# sparrow_ble.net
KiCad netlist of a schematic drawn in EAGLE
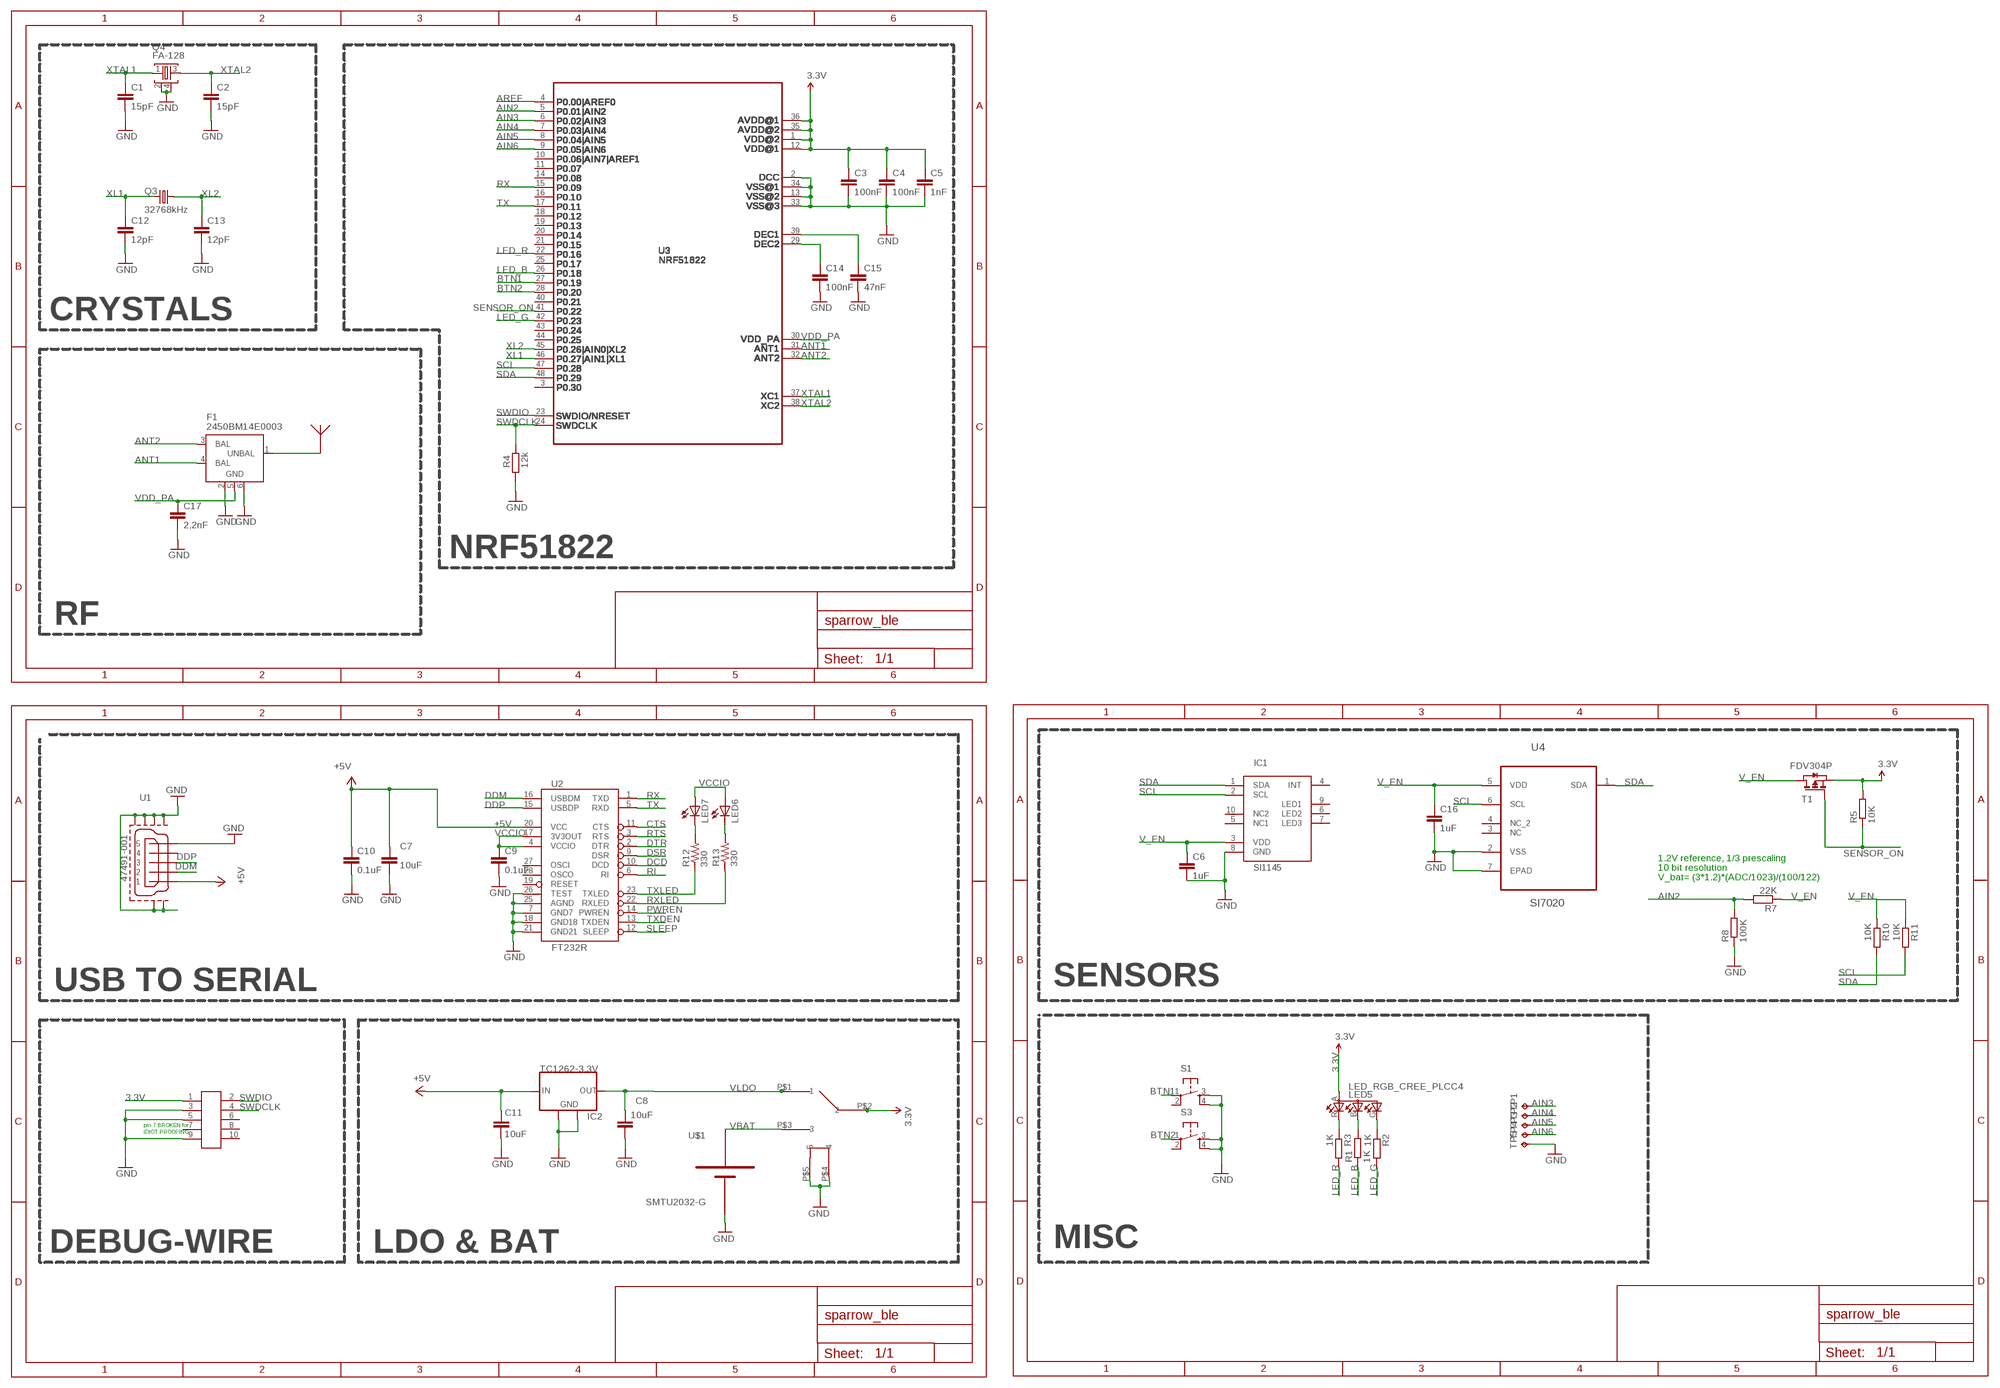
[diagram p0: schematic, sheet 1]

(export (version "E")
  (design (tool "Eeschema 10.0.6"))
  (components
    (comp (ref "C1")
      (value "15pF")
      (footprint "eagle-import:C0402")
      (libsource (lib "eagle-import") (part "resistor_C-EUC0402"))
    )
    (comp (ref "C2")
      (value "15pF")
      (footprint "eagle-import:C0402")
      (libsource (lib "eagle-import") (part "resistor_C-EUC0402"))
    )
    (comp (ref "C3")
      (value "100nF")
      (footprint "eagle-import:C0402")
      (libsource (lib "eagle-import") (part "resistor_C-EUC0402"))
    )
    (comp (ref "C4")
      (value "100nF")
      (footprint "eagle-import:C0402")
      (libsource (lib "eagle-import") (part "resistor_C-EUC0402"))
    )
    (comp (ref "C5")
      (value "1nF")
      (footprint "eagle-import:C0402")
      (libsource (lib "eagle-import") (part "resistor_C-EUC0402"))
    )
    (comp (ref "C6")
      (value "1uF")
      (footprint "eagle-import:C0402")
      (libsource (lib "eagle-import") (part "resistor_C-EUC0402"))
    )
    (comp (ref "C7")
      (value "10uF")
      (footprint "eagle-import:C0402")
      (libsource (lib "eagle-import") (part "C-EUC0402"))
    )
    (comp (ref "C8")
      (value "10uF")
      (footprint "eagle-import:C0402")
      (libsource (lib "eagle-import") (part "C-EUC0402"))
    )
    (comp (ref "C9")
      (value "0.1uF")
      (footprint "eagle-import:0402-CAP")
      (libsource (lib "eagle-import") (part "CAP0402-CAP"))
    )
    (comp (ref "C10")
      (value "0.1uF")
      (footprint "eagle-import:0402-CAP")
      (libsource (lib "eagle-import") (part "CAP0402-CAP"))
    )
    (comp (ref "C11")
      (value "10uF")
      (footprint "eagle-import:C0402")
      (libsource (lib "eagle-import") (part "C-EUC0402"))
    )
    (comp (ref "C12")
      (value "12pF")
      (footprint "eagle-import:C0402")
      (libsource (lib "eagle-import") (part "resistor_C-EUC0402"))
    )
    (comp (ref "C13")
      (value "12pF")
      (footprint "eagle-import:C0402")
      (libsource (lib "eagle-import") (part "resistor_C-EUC0402"))
    )
    (comp (ref "C14")
      (value "100nF")
      (footprint "eagle-import:C0402")
      (libsource (lib "eagle-import") (part "resistor_C-EUC0402"))
    )
    (comp (ref "C15")
      (value "47nF")
      (footprint "eagle-import:C0402")
      (libsource (lib "eagle-import") (part "resistor_C-EUC0402"))
    )
    (comp (ref "C16")
      (value "1uF")
      (footprint "eagle-import:C0402")
      (libsource (lib "eagle-import") (part "resistor_C-EUC0402"))
    )
    (comp (ref "C17")
      (value "2,2nF")
      (footprint "eagle-import:C0402")
      (libsource (lib "eagle-import") (part "resistor_C-EUC0402"))
    )
    (comp (ref "F1")
      (value "2450BM14E0003")
      (footprint "eagle-import:2450BM15A0002")
      (libsource (lib "eagle-import") (part "2450BM15A0002"))
    )
    (comp (ref "IC1")
      (value "SI1145")
      (footprint "eagle-import:QFN10")
      (libsource (lib "eagle-import") (part "SI1145"))
    )
    (comp (ref "IC2")
      (value "TC1262-3.3V")
      (footprint "eagle-import:SOT223")
      (libsource (lib "eagle-import") (part "MCP1825S-SOT223"))
    )
    (comp (ref "J3")
      (value "SMALL_HEADER_5X2")
      (footprint "eagle-import:SAMTEC_5X2")
      (libsource (lib "eagle-import") (part "SMALL_HEADER_5X2"))
    )
    (comp (ref "LED5")
      (value "LED_RGB_CREE_PLCC4")
      (footprint "eagle-import:P-LCC-4-4")
      (libsource (lib "eagle-import") (part "LED_RGB_CREE_PLCC4"))
    )
    (comp (ref "LED6")
      (value "LEDCHIP-LED0603")
      (footprint "eagle-import:CHIP-LED0603")
      (libsource (lib "eagle-import") (part "LEDCHIP-LED0603"))
    )
    (comp (ref "LED7")
      (value "LEDCHIP-LED0603")
      (footprint "eagle-import:CHIP-LED0603")
      (libsource (lib "eagle-import") (part "LEDCHIP-LED0603"))
    )
    (comp (ref "Q3")
      (value "32768kHz")
      (footprint "eagle-import:FC-12M")
      (libsource (lib "eagle-import") (part "FC-12M"))
    )
    (comp (ref "Q4")
      (value "FA-128")
      (footprint "eagle-import:FA-128")
      (libsource (lib "eagle-import") (part "FA-128"))
    )
    (comp (ref "R1")
      (value "1K")
      (footprint "eagle-import:R0402")
      (libsource (lib "eagle-import") (part "R-EU_R0402"))
    )
    (comp (ref "R2")
      (value "1K")
      (footprint "eagle-import:R0402")
      (libsource (lib "eagle-import") (part "R-EU_R0402"))
    )
    (comp (ref "R3")
      (value "1K")
      (footprint "eagle-import:R0402")
      (libsource (lib "eagle-import") (part "R-EU_R0402"))
    )
    (comp (ref "R4")
      (value "12k")
      (footprint "eagle-import:R0402")
      (libsource (lib "eagle-import") (part "resistor_R-EU_R0402"))
    )
    (comp (ref "R5")
      (value "10K")
      (footprint "eagle-import:R0402")
      (libsource (lib "eagle-import") (part "resistor_R-EU_R0402"))
    )
    (comp (ref "R7")
      (value "22K")
      (footprint "eagle-import:R0402")
      (libsource (lib "eagle-import") (part "resistor_R-EU_R0402"))
    )
    (comp (ref "R8")
      (value "100K")
      (footprint "eagle-import:R0402")
      (libsource (lib "eagle-import") (part "resistor_R-EU_R0402"))
    )
    (comp (ref "R10")
      (value "10K")
      (footprint "eagle-import:R0402")
      (libsource (lib "eagle-import") (part "resistor_R-EU_R0402"))
    )
    (comp (ref "R11")
      (value "10K")
      (footprint "eagle-import:R0402")
      (libsource (lib "eagle-import") (part "resistor_R-EU_R0402"))
    )
    (comp (ref "R12")
      (value "330")
      (footprint "eagle-import:0402-RES")
      (libsource (lib "eagle-import") (part "RESISTOR0402-RES"))
    )
    (comp (ref "R13")
      (value "330")
      (footprint "eagle-import:0402-RES")
      (libsource (lib "eagle-import") (part "RESISTOR0402-RES"))
    )
    (comp (ref "S1")
      (value "TAC_SWITCHSMD")
      (footprint "eagle-import:TACTILE-SWITCH-SMD")
      (libsource (lib "eagle-import") (part "TAC_SWITCHSMD"))
    )
    (comp (ref "S3")
      (value "TAC_SWITCHSMD")
      (footprint "eagle-import:TACTILE-SWITCH-SMD")
      (libsource (lib "eagle-import") (part "TAC_SWITCHSMD"))
    )
    (comp (ref "T1")
      (value "FDV304P")
      (footprint "eagle-import:SOT-23")
      (libsource (lib "eagle-import") (part "PMOSSOT23"))
    )
    (comp (ref "TP1")
      (value "TPTP16R")
      (footprint "eagle-import:TP16R")
      (libsource (lib "eagle-import") (part "TPTP16R"))
    )
    (comp (ref "TP2")
      (value "TPTP16R")
      (footprint "eagle-import:TP16R")
      (libsource (lib "eagle-import") (part "TPTP16R"))
    )
    (comp (ref "TP3")
      (value "TPTP16R")
      (footprint "eagle-import:TP16R")
      (libsource (lib "eagle-import") (part "TPTP16R"))
    )
    (comp (ref "TP4")
      (value "TPTP16R")
      (footprint "eagle-import:TP16R")
      (libsource (lib "eagle-import") (part "TPTP16R"))
    )
    (comp (ref "TP5")
      (value "TPTP16R")
      (footprint "eagle-import:TP16R")
      (libsource (lib "eagle-import") (part "TPTP16R"))
    )
    (comp (ref "U$1")
      (value "SMTU2032-G")
      (footprint "eagle-import:SMTU2032-G")
      (libsource (lib "eagle-import") (part "SMTU2032-G"))
    )
    (comp (ref "U$2")
      (value "SWITCH")
      (footprint "eagle-import:PCM12")
      (libsource (lib "eagle-import") (part "SWITCH"))
    )
    (comp (ref "U1")
      (value "47491-001")
      (footprint "eagle-import:47491-0001")
      (libsource (lib "eagle-import") (part "47491-001"))
    )
    (comp (ref "U2")
      (value "FT232R")
      (footprint "eagle-import:SSOP28DB")
      (libsource (lib "eagle-import") (part "FT232RLSSOP"))
    )
    (comp (ref "U3")
      (value "NRF51822")
      (footprint "eagle-import:NRF51822-QFN48")
      (libsource (lib "eagle-import") (part "NRF51822"))
    )
    (comp (ref "U4")
      (value "SI7020")
      (footprint "eagle-import:DFN300X300X110-7N")
      (fields (field (name "MPN") "SHT21"))
      (libsource (lib "eagle-import") (part "SHT21"))
    )
    (comp (ref "U8")
      (value "ANTENNA")
      (footprint "eagle-import:ANTPACK")
      (libsource (lib "eagle-import") (part "ANTENNA"))
    )
  )
  (nets
    (net (code "1") (name "+5V") (class "Default")
      (node (ref "C10") (pin "1") (pinfunction "1_1") (pintype "passive"))
      (node (ref "C11") (pin "1") (pinfunction "1_1") (pintype "passive"))
      (node (ref "C7") (pin "1") (pinfunction "1_1") (pintype "passive"))
      (node (ref "IC2") (pin "1") (pinfunction "IN_1") (pintype "input"))
      (node (ref "U1") (pin "1") (pinfunction "1_1") (pintype "input"))
      (node (ref "U2") (pin "20") (pinfunction "VCC_20") (pintype "power_in"))
    )
    (net (code "2") (name "/AIN2") (class "Default")
      (node (ref "R7") (pin "2") (pinfunction "2_2") (pintype "passive"))
      (node (ref "R8") (pin "2") (pinfunction "2_2") (pintype "passive"))
      (node (ref "U3") (pin "5") (pinfunction "1_5") (pintype "bidirectional"))
    )
    (net (code "3") (name "/AIN3") (class "Default")
      (node (ref "TP1") (pin "TP") (pinfunction "TP_TP") (pintype "input"))
      (node (ref "U3") (pin "6") (pinfunction "1_6") (pintype "bidirectional"))
    )
    (net (code "4") (name "/AIN4") (class "Default")
      (node (ref "TP2") (pin "TP") (pinfunction "TP_TP") (pintype "input"))
      (node (ref "U3") (pin "7") (pinfunction "1_7") (pintype "bidirectional"))
    )
    (net (code "5") (name "/AIN5") (class "Default")
      (node (ref "TP3") (pin "TP") (pinfunction "TP_TP") (pintype "input"))
      (node (ref "U3") (pin "8") (pinfunction "1_8") (pintype "bidirectional"))
    )
    (net (code "6") (name "/AIN6") (class "Default")
      (node (ref "TP4") (pin "TP") (pinfunction "TP_TP") (pintype "input"))
      (node (ref "U3") (pin "9") (pinfunction "1_9") (pintype "bidirectional"))
    )
    (net (code "7") (name "/ANT1") (class "Default")
      (node (ref "F1") (pin "4") (pinfunction "BAL_4") (pintype "passive"))
      (node (ref "U3") (pin "31") (pinfunction "1_31") (pintype "bidirectional"))
    )
    (net (code "8") (name "/ANT2") (class "Default")
      (node (ref "F1") (pin "3") (pinfunction "BAL_3") (pintype "passive"))
      (node (ref "U3") (pin "32") (pinfunction "1_32") (pintype "bidirectional"))
    )
    (net (code "9") (name "/AREF") (class "Default")
      (node (ref "U3") (pin "4") (pinfunction "1_4") (pintype "bidirectional"))
    )
    (net (code "10") (name "/BTN1") (class "Default")
      (node (ref "S1") (pin "1") (pinfunction "1_1") (pintype "passive"))
      (node (ref "U3") (pin "27") (pinfunction "1_27") (pintype "bidirectional"))
    )
    (net (code "11") (name "/BTN2") (class "Default")
      (node (ref "S3") (pin "1") (pinfunction "1_1") (pintype "passive"))
      (node (ref "U3") (pin "28") (pinfunction "1_28") (pintype "bidirectional"))
    )
    (net (code "12") (name "/CTS") (class "Default")
      (node (ref "U2") (pin "11") (pinfunction "CTS_11") (pintype "input"))
    )
    (net (code "13") (name "/DCD") (class "Default")
      (node (ref "U2") (pin "10") (pinfunction "DCD_10") (pintype "input"))
    )
    (net (code "14") (name "/DDM") (class "Default")
      (node (ref "U1") (pin "2") (pinfunction "2_2") (pintype "input"))
      (node (ref "U2") (pin "16") (pinfunction "USBDM_16") (pintype "bidirectional"))
    )
    (net (code "15") (name "/DDP") (class "Default")
      (node (ref "U1") (pin "3") (pinfunction "3_3") (pintype "input"))
      (node (ref "U2") (pin "15") (pinfunction "USBDP_15") (pintype "bidirectional"))
    )
    (net (code "16") (name "/DSR") (class "Default")
      (node (ref "U2") (pin "9") (pinfunction "DSR_9") (pintype "input"))
    )
    (net (code "17") (name "/DTR") (class "Default")
      (node (ref "U2") (pin "2") (pinfunction "DTR_2") (pintype "output"))
    )
    (net (code "18") (name "/LED_B") (class "Default")
      (node (ref "R1") (pin "1") (pinfunction "1_1") (pintype "passive"))
      (node (ref "U3") (pin "26") (pinfunction "1_26") (pintype "bidirectional"))
    )
    (net (code "19") (name "/LED_G") (class "Default")
      (node (ref "R2") (pin "2") (pinfunction "2_2") (pintype "passive"))
      (node (ref "U3") (pin "42") (pinfunction "1_42") (pintype "bidirectional"))
    )
    (net (code "20") (name "/LED_R") (class "Default")
      (node (ref "R3") (pin "2") (pinfunction "2_2") (pintype "passive"))
      (node (ref "U3") (pin "22") (pinfunction "1_22") (pintype "bidirectional"))
    )
    (net (code "21") (name "/PWREN") (class "Default")
      (node (ref "U2") (pin "14") (pinfunction "PWREN_14") (pintype "input"))
    )
    (net (code "22") (name "/RI") (class "Default")
      (node (ref "U2") (pin "6") (pinfunction "RI_6") (pintype "input"))
    )
    (net (code "23") (name "/RTS") (class "Default")
      (node (ref "U2") (pin "3") (pinfunction "RTS_3") (pintype "output"))
    )
    (net (code "24") (name "/RX") (class "Default")
      (node (ref "U2") (pin "1") (pinfunction "TXD_1") (pintype "output"))
      (node (ref "U3") (pin "15") (pinfunction "1_15") (pintype "bidirectional"))
    )
    (net (code "25") (name "/RXLED") (class "Default")
      (node (ref "R13") (pin "1") (pinfunction "1_1") (pintype "passive"))
      (node (ref "U2") (pin "22") (pinfunction "RXLED_22") (pintype "input"))
    )
    (net (code "26") (name "/SCL") (class "Default")
      (node (ref "IC1") (pin "2") (pinfunction "SCL_2") (pintype "bidirectional"))
      (node (ref "R11") (pin "2") (pinfunction "2_2") (pintype "passive"))
      (node (ref "U3") (pin "47") (pinfunction "1_47") (pintype "bidirectional"))
      (node (ref "U4") (pin "6") (pinfunction "SCL_6") (pintype "input"))
    )
    (net (code "27") (name "/SDA") (class "Default")
      (node (ref "IC1") (pin "1") (pinfunction "SDA_1") (pintype "bidirectional"))
      (node (ref "R10") (pin "2") (pinfunction "2_2") (pintype "passive"))
      (node (ref "U3") (pin "48") (pinfunction "1_48") (pintype "bidirectional"))
      (node (ref "U4") (pin "1") (pinfunction "SDA_1") (pintype "bidirectional"))
    )
    (net (code "28") (name "/SENSOR_ON") (class "Default")
      (node (ref "R5") (pin "1") (pinfunction "1_1") (pintype "passive"))
      (node (ref "T1") (pin "3") (pinfunction "G_3") (pintype "passive"))
      (node (ref "U3") (pin "41") (pinfunction "1_41") (pintype "bidirectional"))
    )
    (net (code "29") (name "/SLEEP") (class "Default")
      (node (ref "U2") (pin "12") (pinfunction "SLEEP_12") (pintype "input"))
    )
    (net (code "30") (name "/SWDCLK") (class "Default")
      (node (ref "J3") (pin "4") (pinfunction "P$4_4") (pintype "bidirectional"))
      (node (ref "R4") (pin "2") (pinfunction "2_2") (pintype "passive"))
      (node (ref "U3") (pin "24") (pinfunction "1_24") (pintype "bidirectional"))
    )
    (net (code "31") (name "/SWDIO") (class "Default")
      (node (ref "J3") (pin "2") (pinfunction "P$2_2") (pintype "bidirectional"))
      (node (ref "U3") (pin "23") (pinfunction "1_23") (pintype "bidirectional"))
    )
    (net (code "32") (name "/TX") (class "Default")
      (node (ref "U2") (pin "5") (pinfunction "RXD_5") (pintype "input"))
      (node (ref "U3") (pin "17") (pinfunction "1_17") (pintype "bidirectional"))
    )
    (net (code "33") (name "/TXDEN") (class "Default")
      (node (ref "U2") (pin "13") (pinfunction "TXDEN_13") (pintype "input"))
    )
    (net (code "34") (name "/TXLED") (class "Default")
      (node (ref "R12") (pin "1") (pinfunction "1_1") (pintype "passive"))
      (node (ref "U2") (pin "23") (pinfunction "TXLED_23") (pintype "input"))
    )
    (net (code "35") (name "/VBAT") (class "Default")
      (node (ref "U$1") (pin "1") (pinfunction "P$1_1") (pintype "bidirectional"))
      (node (ref "U$2") (pin "P$3") (pinfunction "3_P$3") (pintype "bidirectional"))
    )
    (net (code "36") (name "/VCCIO") (class "Default")
      (node (ref "C9") (pin "1") (pinfunction "1_1") (pintype "passive"))
      (node (ref "LED6") (pin "A") (pinfunction "A_A") (pintype "passive"))
      (node (ref "LED7") (pin "A") (pinfunction "A_A") (pintype "passive"))
      (node (ref "U2") (pin "17") (pinfunction "3V3OUT_17") (pintype "output"))
      (node (ref "U2") (pin "4") (pinfunction "VCCIO_4") (pintype "power_in"))
    )
    (net (code "37") (name "/VDD_PA") (class "Default")
      (node (ref "C17") (pin "1") (pinfunction "1_1") (pintype "passive"))
      (node (ref "F1") (pin "5") (pinfunction "GND_5") (pintype "passive"))
      (node (ref "U3") (pin "30") (pinfunction "1_30") (pintype "output"))
    )
    (net (code "38") (name "/VLDO") (class "Default")
      (node (ref "C8") (pin "1") (pinfunction "1_1") (pintype "passive"))
      (node (ref "IC2") (pin "3") (pinfunction "OUT_3") (pintype "output"))
      (node (ref "U$2") (pin "P$1") (pinfunction "1_P$1") (pintype "bidirectional"))
    )
    (net (code "39") (name "/V_EN") (class "Default")
      (node (ref "C16") (pin "1") (pinfunction "1_1") (pintype "passive"))
      (node (ref "C6") (pin "1") (pinfunction "1_1") (pintype "passive"))
      (node (ref "IC1") (pin "3") (pinfunction "VDD_3") (pintype "bidirectional"))
      (node (ref "R10") (pin "1") (pinfunction "1_1") (pintype "passive"))
      (node (ref "R11") (pin "1") (pinfunction "1_1") (pintype "passive"))
      (node (ref "R7") (pin "1") (pinfunction "1_1") (pintype "passive"))
      (node (ref "T1") (pin "1") (pinfunction "D_1") (pintype "passive"))
      (node (ref "U4") (pin "5") (pinfunction "VDD_5") (pintype "power_in"))
    )
    (net (code "40") (name "/XL1") (class "Default")
      (node (ref "C12") (pin "1") (pinfunction "1_1") (pintype "passive"))
      (node (ref "Q3") (pin "2") (pinfunction "2_2") (pintype "passive"))
      (node (ref "U3") (pin "46") (pinfunction "1_46") (pintype "bidirectional"))
    )
    (net (code "41") (name "/XL2") (class "Default")
      (node (ref "C13") (pin "1") (pinfunction "1_1") (pintype "passive"))
      (node (ref "Q3") (pin "1") (pinfunction "1_1") (pintype "passive"))
      (node (ref "U3") (pin "45") (pinfunction "1_45") (pintype "bidirectional"))
    )
    (net (code "42") (name "/XTAL1") (class "Default")
      (node (ref "C1") (pin "1") (pinfunction "1_1") (pintype "passive"))
      (node (ref "Q4") (pin "1") (pinfunction "1_1") (pintype "passive"))
      (node (ref "U3") (pin "37") (pinfunction "1_37") (pintype "bidirectional"))
    )
    (net (code "43") (name "/XTAL2") (class "Default")
      (node (ref "C2") (pin "1") (pinfunction "1_1") (pintype "passive"))
      (node (ref "Q4") (pin "3") (pinfunction "3_3") (pintype "passive"))
      (node (ref "U3") (pin "38") (pinfunction "1_38") (pintype "bidirectional"))
    )
    (net (code "44") (name "3.3V") (class "Default")
      (node (ref "C3") (pin "1") (pinfunction "1_1") (pintype "passive"))
      (node (ref "C4") (pin "1") (pinfunction "1_1") (pintype "passive"))
      (node (ref "C5") (pin "1") (pinfunction "1_1") (pintype "passive"))
      (node (ref "J3") (pin "1") (pinfunction "P$1_1") (pintype "bidirectional"))
      (node (ref "LED5") (pin "A") (pinfunction "A2_A") (pintype "passive"))
      (node (ref "R5") (pin "2") (pinfunction "2_2") (pintype "passive"))
      (node (ref "T1") (pin "2") (pinfunction "S_2") (pintype "passive"))
      (node (ref "U$2") (pin "P$2") (pinfunction "2_P$2") (pintype "bidirectional"))
      (node (ref "U3") (pin "1") (pinfunction "1_1") (pintype "input"))
      (node (ref "U3") (pin "12") (pinfunction "1_12") (pintype "input"))
      (node (ref "U3") (pin "35") (pinfunction "1_35") (pintype "input"))
      (node (ref "U3") (pin "36") (pinfunction "1_36") (pintype "input"))
    )
    (net (code "45") (name "GND") (class "Default")
      (node (ref "C1") (pin "2") (pinfunction "2_2") (pintype "passive"))
      (node (ref "C10") (pin "2") (pinfunction "2_2") (pintype "passive"))
      (node (ref "C11") (pin "2") (pinfunction "2_2") (pintype "passive"))
      (node (ref "C12") (pin "2") (pinfunction "2_2") (pintype "passive"))
      (node (ref "C13") (pin "2") (pinfunction "2_2") (pintype "passive"))
      (node (ref "C14") (pin "2") (pinfunction "2_2") (pintype "passive"))
      (node (ref "C15") (pin "2") (pinfunction "2_2") (pintype "passive"))
      (node (ref "C16") (pin "2") (pinfunction "2_2") (pintype "passive"))
      (node (ref "C17") (pin "2") (pinfunction "2_2") (pintype "passive"))
      (node (ref "C2") (pin "2") (pinfunction "2_2") (pintype "passive"))
      (node (ref "C3") (pin "2") (pinfunction "2_2") (pintype "passive"))
      (node (ref "C4") (pin "2") (pinfunction "2_2") (pintype "passive"))
      (node (ref "C5") (pin "2") (pinfunction "2_2") (pintype "passive"))
      (node (ref "C6") (pin "2") (pinfunction "2_2") (pintype "passive"))
      (node (ref "C7") (pin "2") (pinfunction "2_2") (pintype "passive"))
      (node (ref "C8") (pin "2") (pinfunction "2_2") (pintype "passive"))
      (node (ref "C9") (pin "2") (pinfunction "2_2") (pintype "passive"))
      (node (ref "F1") (pin "2") (pinfunction "GND_2") (pintype "passive"))
      (node (ref "F1") (pin "6") (pinfunction "GND_6") (pintype "passive"))
      (node (ref "IC1") (pin "8") (pinfunction "GND_8") (pintype "bidirectional"))
      (node (ref "IC2") (pin "2") (pinfunction "GND_2") (pintype "power_in"))
      (node (ref "IC2") (pin "4") (pinfunction "GND_4") (pintype "power_in"))
      (node (ref "J3") (pin "3") (pinfunction "P$3_3") (pintype "bidirectional"))
      (node (ref "J3") (pin "5") (pinfunction "P$5_5") (pintype "bidirectional"))
      (node (ref "J3") (pin "9") (pinfunction "P$9_9") (pintype "bidirectional"))
      (node (ref "Q4") (pin "2") (pinfunction "2_2") (pintype "passive"))
      (node (ref "Q4") (pin "4") (pinfunction "4_4") (pintype "passive"))
      (node (ref "R4") (pin "1") (pinfunction "1_1") (pintype "passive"))
      (node (ref "R8") (pin "1") (pinfunction "1_1") (pintype "passive"))
      (node (ref "S1") (pin "3") (pinfunction "3_3") (pintype "passive"))
      (node (ref "S1") (pin "4") (pinfunction "4_4") (pintype "passive"))
      (node (ref "S3") (pin "3") (pinfunction "3_3") (pintype "passive"))
      (node (ref "S3") (pin "4") (pinfunction "4_4") (pintype "passive"))
      (node (ref "TP5") (pin "TP") (pinfunction "TP_TP") (pintype "input"))
      (node (ref "U$1") (pin "2") (pinfunction "P$2_2") (pintype "bidirectional"))
      (node (ref "U$2") (pin "P$4") (pinfunction "4_P$4") (pintype "bidirectional"))
      (node (ref "U$2") (pin "P$5") (pinfunction "5_P$5") (pintype "bidirectional"))
      (node (ref "U1") (pin "5") (pinfunction "5_5") (pintype "input"))
      (node (ref "U1") (pin "GND1") (pinfunction "GND1_GND1") (pintype "bidirectional"))
      (node (ref "U1") (pin "GND2") (pinfunction "GND2_GND2") (pintype "bidirectional"))
      (node (ref "U1") (pin "GND3") (pinfunction "GND3_GND3") (pintype "bidirectional"))
      (node (ref "U1") (pin "GND4") (pinfunction "GND4_GND4") (pintype "bidirectional"))
      (node (ref "U1") (pin "GND5") (pinfunction "GND5_GND5") (pintype "bidirectional"))
      (node (ref "U1") (pin "GND6") (pinfunction "GND6_GND6") (pintype "bidirectional"))
      (node (ref "U2") (pin "18") (pinfunction "GND18_18") (pintype "power_in"))
      (node (ref "U2") (pin "21") (pinfunction "GND21_21") (pintype "power_in"))
      (node (ref "U2") (pin "25") (pinfunction "AGND_25") (pintype "power_in"))
      (node (ref "U2") (pin "26") (pinfunction "TEST_26") (pintype "input"))
      (node (ref "U2") (pin "7") (pinfunction "GND7_7") (pintype "power_in"))
      (node (ref "U3") (pin "13") (pinfunction "1_13") (pintype "input"))
      (node (ref "U3") (pin "2") (pinfunction "1_2") (pintype "input"))
      (node (ref "U3") (pin "33") (pinfunction "1_33") (pintype "input"))
      (node (ref "U3") (pin "34") (pinfunction "1_34") (pintype "input"))
      (node (ref "U4") (pin "2") (pinfunction "VSS_2") (pintype "power_in"))
      (node (ref "U4") (pin "7") (pinfunction "EPAD_7") (pintype "passive"))
    )
    (net (code "46") (name "Net-(F1-UNBAL)") (class "Default")
      (node (ref "F1") (pin "1") (pinfunction "UNBAL_1") (pintype "passive"))
      (node (ref "U8") (pin "P$1") (pinfunction "P$1_P$1") (pintype "bidirectional"))
    )
    (net (code "47") (name "Net-(LED5-CBLUE)") (class "Default")
      (node (ref "LED5") (pin "B") (pinfunction "CBLUE_B") (pintype "passive"))
      (node (ref "R1") (pin "2") (pinfunction "2_2") (pintype "passive"))
    )
    (net (code "48") (name "Net-(LED5-CGREEN)") (class "Default")
      (node (ref "LED5") (pin "G") (pinfunction "CGREEN_G") (pintype "passive"))
      (node (ref "R2") (pin "1") (pinfunction "1_1") (pintype "passive"))
    )
    (net (code "49") (name "Net-(LED5-CRED)") (class "Default")
      (node (ref "LED5") (pin "R") (pinfunction "CRED_R") (pintype "passive"))
      (node (ref "R3") (pin "1") (pinfunction "1_1") (pintype "passive"))
    )
    (net (code "50") (name "Net-(LED6-PadC)") (class "Default")
      (node (ref "LED6") (pin "C") (pinfunction "C_C") (pintype "passive"))
      (node (ref "R13") (pin "2") (pinfunction "2_2") (pintype "passive"))
    )
    (net (code "51") (name "Net-(LED7-PadC)") (class "Default")
      (node (ref "LED7") (pin "C") (pinfunction "C_C") (pintype "passive"))
      (node (ref "R12") (pin "2") (pinfunction "2_2") (pintype "passive"))
    )
    (net (code "52") (name "Net-(U3F-1)") (class "Default")
      (node (ref "C15") (pin "1") (pinfunction "1_1") (pintype "passive"))
      (node (ref "U3") (pin "39") (pinfunction "1_39") (pintype "output"))
    )
    (net (code "53") (name "Net-(U3G-1)") (class "Default")
      (node (ref "C14") (pin "1") (pinfunction "1_1") (pintype "passive"))
      (node (ref "U3") (pin "29") (pinfunction "1_29") (pintype "output"))
    )
    (net (code "54") (name "unconnected-(IC1-INT-Pad4)") (class "Default")
      (node (ref "IC1") (pin "4") (pinfunction "INT_4") (pintype "bidirectional"))
    )
    (net (code "55") (name "unconnected-(IC1-LED1-Pad9)") (class "Default")
      (node (ref "IC1") (pin "9") (pinfunction "LED1_9") (pintype "bidirectional"))
    )
    (net (code "56") (name "unconnected-(IC1-LED2-Pad6)") (class "Default")
      (node (ref "IC1") (pin "6") (pinfunction "LED2_6") (pintype "bidirectional"))
    )
    (net (code "57") (name "unconnected-(IC1-LED3-Pad7)") (class "Default")
      (node (ref "IC1") (pin "7") (pinfunction "LED3_7") (pintype "bidirectional"))
    )
    (net (code "58") (name "unconnected-(IC1-NC1-Pad5)") (class "Default")
      (node (ref "IC1") (pin "5") (pinfunction "NC1_5") (pintype "no_connect"))
    )
    (net (code "59") (name "unconnected-(IC1-NC2-Pad10)") (class "Default")
      (node (ref "IC1") (pin "10") (pinfunction "NC2_10") (pintype "no_connect"))
    )
    (net (code "60") (name "unconnected-(J3-P$6-Pad6)") (class "Default")
      (node (ref "J3") (pin "6") (pinfunction "P$6_6") (pintype "bidirectional"))
    )
    (net (code "61") (name "unconnected-(J3-P$7-Pad7)") (class "Default")
      (node (ref "J3") (pin "7") (pinfunction "P$7_7") (pintype "bidirectional"))
    )
    (net (code "62") (name "unconnected-(J3-P$8-Pad8)") (class "Default")
      (node (ref "J3") (pin "8") (pinfunction "P$8_8") (pintype "bidirectional"))
    )
    (net (code "63") (name "unconnected-(J3-P$10-Pad10)") (class "Default")
      (node (ref "J3") (pin "10") (pinfunction "P$10_10") (pintype "bidirectional"))
    )
    (net (code "64") (name "unconnected-(S1-Pad2)") (class "Default")
      (node (ref "S1") (pin "2") (pinfunction "2_2") (pintype "passive"))
    )
    (net (code "65") (name "unconnected-(S3-Pad2)") (class "Default")
      (node (ref "S3") (pin "2") (pinfunction "2_2") (pintype "passive"))
    )
    (net (code "66") (name "unconnected-(U1-Pad4)") (class "Default")
      (node (ref "U1") (pin "4") (pinfunction "4_4") (pintype "input"))
    )
    (net (code "67") (name "unconnected-(U2-OSCI-Pad27)") (class "Default")
      (node (ref "U2") (pin "27") (pinfunction "OSCI_27") (pintype "input"))
    )
    (net (code "68") (name "unconnected-(U2-OSCO-Pad28)") (class "Default")
      (node (ref "U2") (pin "28") (pinfunction "OSCO_28") (pintype "output"))
    )
    (net (code "69") (name "unconnected-(U2-RESET-Pad19)") (class "Default")
      (node (ref "U2") (pin "19") (pinfunction "RESET_19") (pintype "input"))
    )
    (net (code "70") (name "unconnected-(U3AC-1-Pad40)") (class "Default")
      (node (ref "U3") (pin "40") (pinfunction "1_40") (pintype "bidirectional"))
    )
    (net (code "71") (name "unconnected-(U3AF-1-Pad43)") (class "Default")
      (node (ref "U3") (pin "43") (pinfunction "1_43") (pintype "bidirectional"))
    )
    (net (code "72") (name "unconnected-(U3AG-1-Pad44)") (class "Default")
      (node (ref "U3") (pin "44") (pinfunction "1_44") (pintype "bidirectional"))
    )
    (net (code "73") (name "unconnected-(U3AL-1-Pad3)") (class "Default")
      (node (ref "U3") (pin "3") (pinfunction "1_3") (pintype "bidirectional"))
    )
    (net (code "74") (name "unconnected-(U3N-1-Pad10)") (class "Default")
      (node (ref "U3") (pin "10") (pinfunction "1_10") (pintype "bidirectional"))
    )
    (net (code "75") (name "unconnected-(U3O-1-Pad11)") (class "Default")
      (node (ref "U3") (pin "11") (pinfunction "1_11") (pintype "bidirectional"))
    )
    (net (code "76") (name "unconnected-(U3P-1-Pad14)") (class "Default")
      (node (ref "U3") (pin "14") (pinfunction "1_14") (pintype "bidirectional"))
    )
    (net (code "77") (name "unconnected-(U3R-1-Pad16)") (class "Default")
      (node (ref "U3") (pin "16") (pinfunction "1_16") (pintype "bidirectional"))
    )
    (net (code "78") (name "unconnected-(U3T-1-Pad18)") (class "Default")
      (node (ref "U3") (pin "18") (pinfunction "1_18") (pintype "bidirectional"))
    )
    (net (code "79") (name "unconnected-(U3U-1-Pad19)") (class "Default")
      (node (ref "U3") (pin "19") (pinfunction "1_19") (pintype "bidirectional"))
    )
    (net (code "80") (name "unconnected-(U3V-1-Pad20)") (class "Default")
      (node (ref "U3") (pin "20") (pinfunction "1_20") (pintype "bidirectional"))
    )
    (net (code "81") (name "unconnected-(U3W-1-Pad21)") (class "Default")
      (node (ref "U3") (pin "21") (pinfunction "1_21") (pintype "bidirectional"))
    )
    (net (code "82") (name "unconnected-(U3Y-1-Pad25)") (class "Default")
      (node (ref "U3") (pin "25") (pinfunction "1_25") (pintype "bidirectional"))
    )
    (net (code "83") (name "unconnected-(U4-NC-Pad3)") (class "Default")
      (node (ref "U4") (pin "3") (pinfunction "NC_3") (pintype "no_connect"))
    )
    (net (code "84") (name "unconnected-(U4-NC_2-Pad4)") (class "Default")
      (node (ref "U4") (pin "4") (pinfunction "NC_2_4") (pintype "no_connect"))
    )
  )
)
